# encoder_module_boardedge_pad.net
KiCad netlist of a schematic drawn in EAGLE
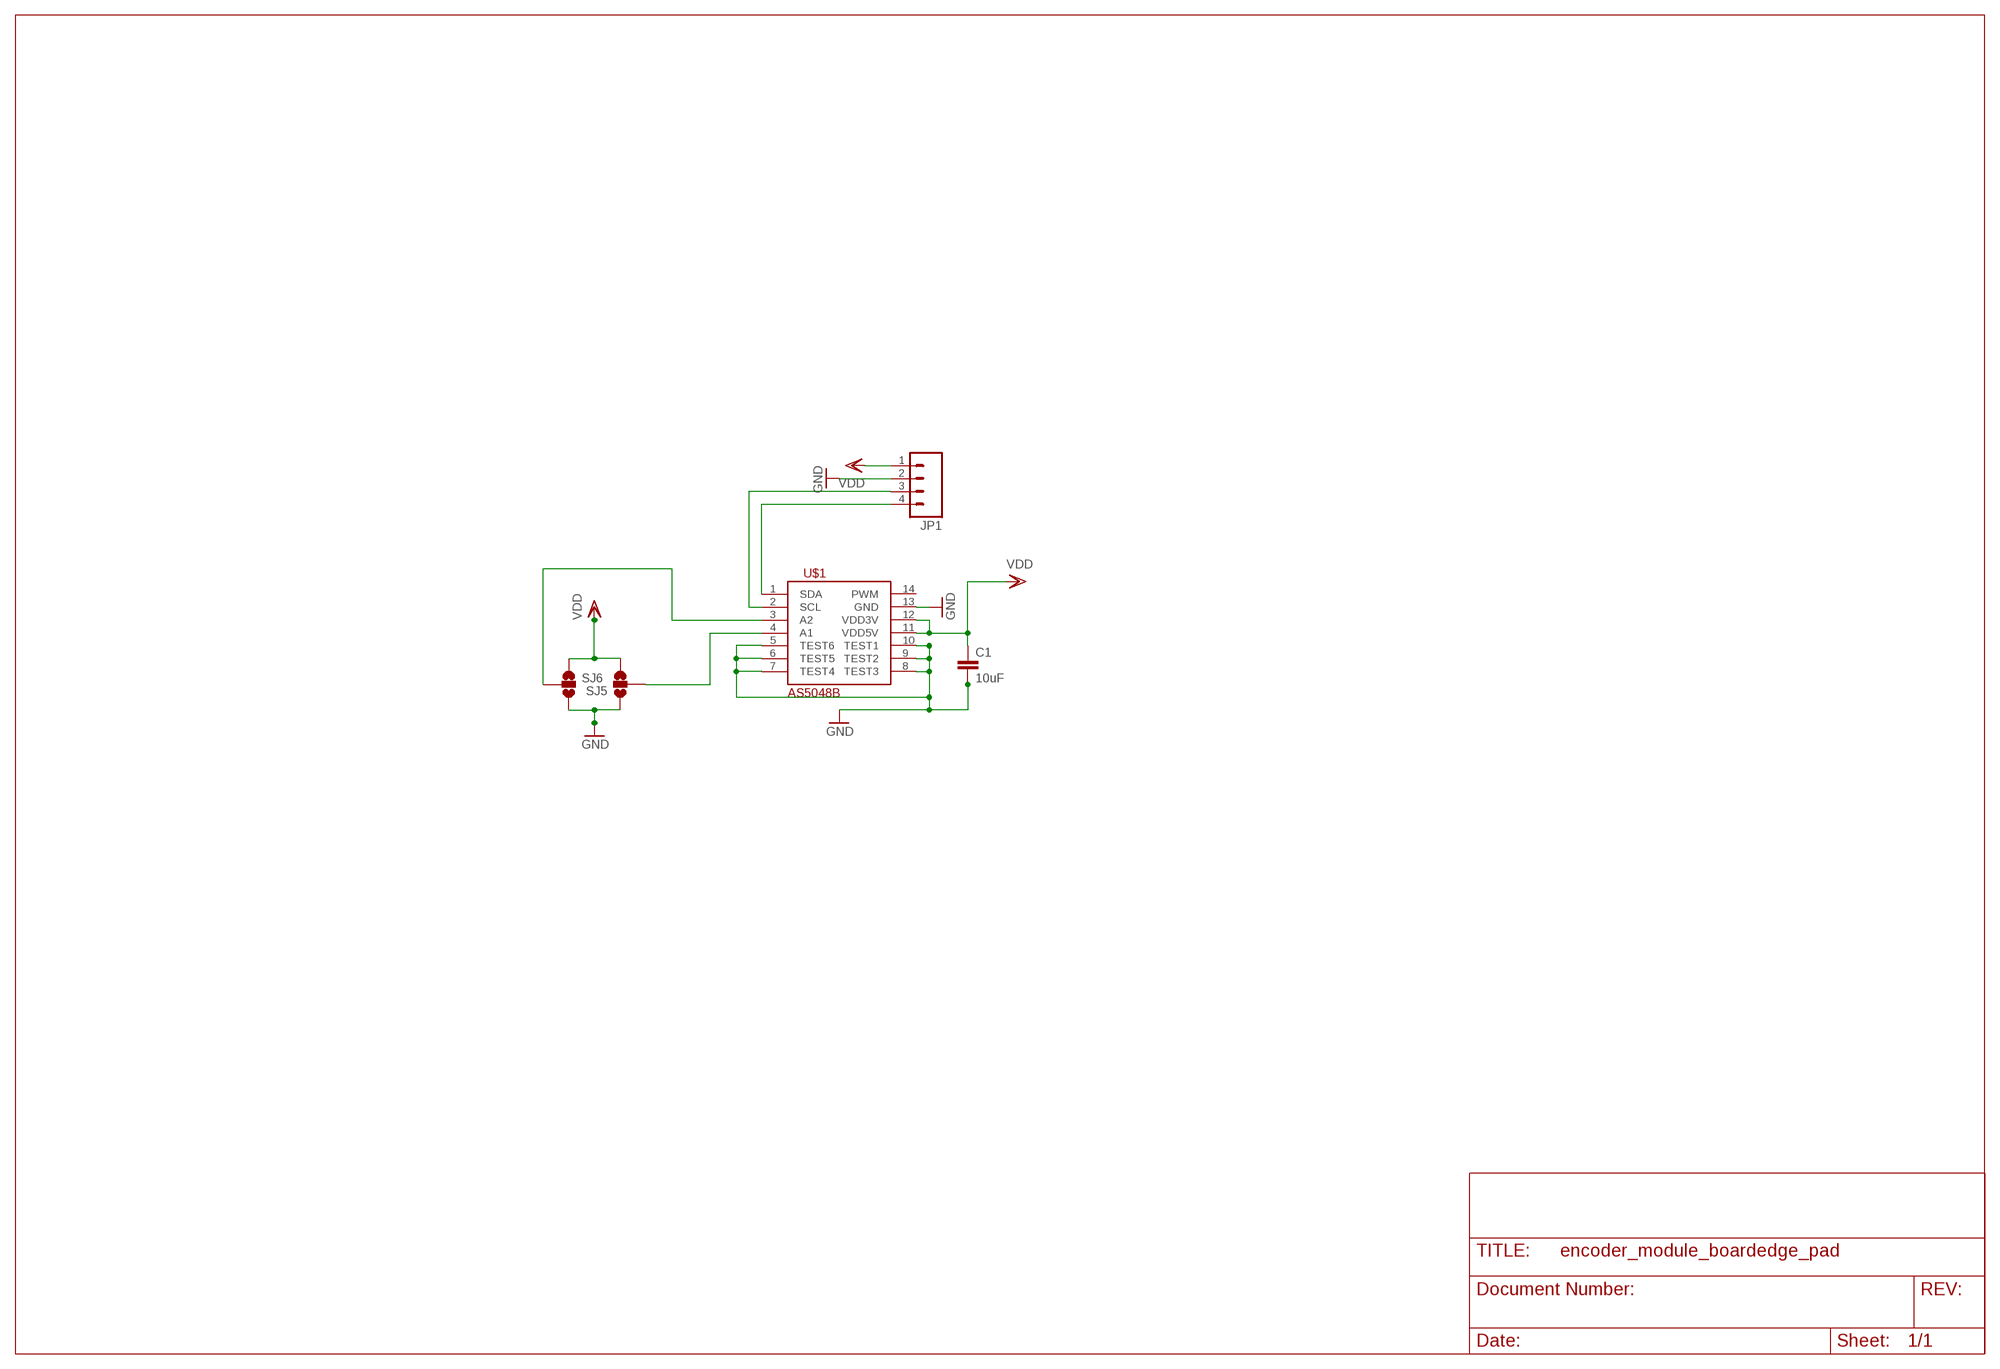
[diagram p0: schematic, sheet 1]

(export (version "E")
  (design (tool "Eeschema 10.0.6"))
  (components
    (comp (ref "C1")
      (value "10uF")
      (footprint "eagle-import:0603-CAP")
      (fields (field (name "VOLTAGE") "6.3V"))
      (libsource (lib "eagle-import") (part "CAP0603-CAP"))
    )
    (comp (ref "JP1")
      (value "M04BOARDEDGE_VERT")
      (footprint "eagle-import:1X4_3MM_BOARDEDGE_VERT")
      (libsource (lib "eagle-import") (part "M04BOARDEDGE_VERT"))
    )
    (comp (ref "SJ5")
      (value "SOLDERJUMPER_2WAYS")
      (footprint "eagle-import:SJ_3")
      (libsource (lib "eagle-import") (part "SOLDERJUMPER_2WAYS"))
    )
    (comp (ref "SJ6")
      (value "SOLDERJUMPER_2WAYS")
      (footprint "eagle-import:SJ_3")
      (libsource (lib "eagle-import") (part "SOLDERJUMPER_2WAYS"))
    )
    (comp (ref "U$1")
      (value "AS5048B")
      (footprint "eagle-import:TSSOP14")
      (libsource (lib "eagle-import") (part "AS5048B"))
    )
  )
  (nets
    (net (code "1") (name "GND") (class "Default")
      (node (ref "C1") (pin "2") (pinfunction "2_2") (pintype "passive"))
      (node (ref "JP1") (pin "2") (pinfunction "2_2") (pintype "passive"))
      (node (ref "SJ5") (pin "1") (pinfunction "1_1") (pintype "passive"))
      (node (ref "SJ6") (pin "3") (pinfunction "3_3") (pintype "passive"))
      (node (ref "U$1") (pin "10") (pinfunction "TEST1_10") (pintype "bidirectional"))
      (node (ref "U$1") (pin "13") (pinfunction "GND_13") (pintype "bidirectional"))
      (node (ref "U$1") (pin "5") (pinfunction "TEST6_5") (pintype "bidirectional"))
      (node (ref "U$1") (pin "6") (pinfunction "TEST5_6") (pintype "bidirectional"))
      (node (ref "U$1") (pin "7") (pinfunction "TEST4_7") (pintype "bidirectional"))
      (node (ref "U$1") (pin "8") (pinfunction "TEST3_8") (pintype "bidirectional"))
      (node (ref "U$1") (pin "9") (pinfunction "TEST2_9") (pintype "bidirectional"))
    )
    (net (code "2") (name "Net-(U$1-A1)") (class "Default")
      (node (ref "SJ5") (pin "2") (pinfunction "2_2") (pintype "passive"))
      (node (ref "U$1") (pin "4") (pinfunction "A1_4") (pintype "bidirectional"))
    )
    (net (code "3") (name "Net-(U$1-A2)") (class "Default")
      (node (ref "SJ6") (pin "2") (pinfunction "2_2") (pintype "passive"))
      (node (ref "U$1") (pin "3") (pinfunction "A2_3") (pintype "bidirectional"))
    )
    (net (code "4") (name "Net-(U$1-SCL)") (class "Default")
      (node (ref "JP1") (pin "3") (pinfunction "3_3") (pintype "passive"))
      (node (ref "U$1") (pin "2") (pinfunction "SCL_2") (pintype "bidirectional"))
    )
    (net (code "5") (name "Net-(U$1-SDA)") (class "Default")
      (node (ref "JP1") (pin "4") (pinfunction "4_4") (pintype "passive"))
      (node (ref "U$1") (pin "1") (pinfunction "SDA_1") (pintype "bidirectional"))
    )
    (net (code "6") (name "VDD") (class "Default")
      (node (ref "C1") (pin "1") (pinfunction "1_1") (pintype "passive"))
      (node (ref "JP1") (pin "1") (pinfunction "1_1") (pintype "passive"))
      (node (ref "SJ5") (pin "3") (pinfunction "3_3") (pintype "passive"))
      (node (ref "SJ6") (pin "1") (pinfunction "1_1") (pintype "passive"))
      (node (ref "U$1") (pin "11") (pinfunction "VDD5V_11") (pintype "bidirectional"))
      (node (ref "U$1") (pin "12") (pinfunction "VDD3V_12") (pintype "bidirectional"))
    )
    (net (code "7") (name "unconnected-(U$1-PWM-Pad14)") (class "Default")
      (node (ref "U$1") (pin "14") (pinfunction "PWM_14") (pintype "bidirectional"))
    )
  )
)
